# Sheet2.net
KiCad netlist of a schematic drawn in Altium Designer
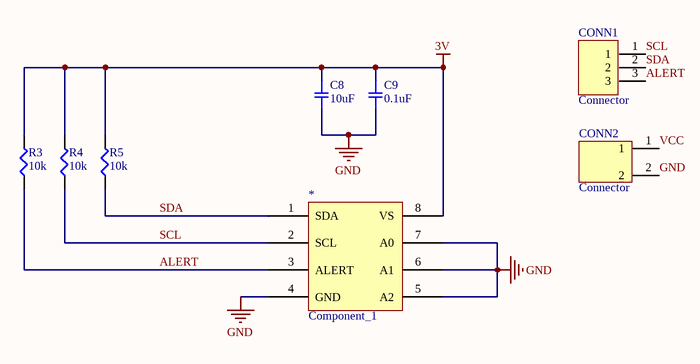
[diagram p0: Sheet2.SchDoc]

(export (version "E")
  (design (tool "Eeschema 10.0.6"))
  (components
    (comp (ref "*")
      (value "Component_1")
      (footprint "TMP75C")
      (libsource (lib "TMP75C") (part "Component_1"))
    )
    (comp (ref "C8")
      (value "10uF")
      (footprint "SMD-0805C")
      (description "Cap Ceramic 10uF 25V X5R 10% 0805")
      (fields
        (field (name "PART NUMBER") "CL21A106KAFN3NE")
        (field (name "MANUFACTURER") "Samsung Electro-Mechanics")
      )
      (libsource (lib "capacitor_0805") (part "CL21A106KAFN3NE"))
    )
    (comp (ref "C9")
      (value "0.1uF")
      (footprint "SMD-0805C")
      (description "CAP CER 0.1uF 50V X7T 0805")
      (fields
        (field (name "PART NUMBER") "GC321AD72E103KX01D")
        (field (name "MANUFACTURER") "Samsung Electro-Mechanics")
      )
      (libsource (lib "capacitor_0805") (part "CL21B104JBCNNNC"))
    )
    (comp (ref "CONN1")
      (value "Connector")
      (footprint "1x3x2.54 Pin Header TH V")
      (libsource (lib "Connectors") (part "Header 1x3"))
    )
    (comp (ref "CONN2")
      (value "Connector")
      (footprint "1x2x2.54 Pin Header TH V")
      (libsource (lib "Connectors") (part "Header 1x2"))
    )
    (comp (ref "R3")
      (value "10k")
      (footprint "SMD-0805-RES")
      (description "RES SMD 10K OHM 5% 1/2W 0805")
      (fields (field (name "PART NUMBER") "ERJ-P6WJ103V") (field (name "DIGI-KEY PART NUMBER") "P16966CT-ND"))
      (libsource (lib "Panasonic_ERJ_0805") (part "ERJ-P6WJ103V"))
    )
    (comp (ref "R4")
      (value "10k")
      (footprint "SMD-0805-RES")
      (description "RES SMD 10K OHM 5% 1/2W 0805")
      (fields (field (name "PART NUMBER") "ERJ-P6WJ103V") (field (name "DIGI-KEY PART NUMBER") "P16966CT-ND"))
      (libsource (lib "Panasonic_ERJ_0805") (part "ERJ-P6WJ103V"))
    )
    (comp (ref "R5")
      (value "10k")
      (footprint "SMD-0805-RES")
      (description "RES SMD 10K OHM 5% 1/2W 0805")
      (fields (field (name "PART NUMBER") "ERJ-P6WJ103V") (field (name "DIGI-KEY PART NUMBER") "P16966CT-ND"))
      (libsource (lib "Panasonic_ERJ_0805") (part "ERJ-P6WJ103V"))
    )
  )
  (nets
    (net (code "1") (name "/ALERT") (class "Default")
      (node (ref "*") (pin "3") (pinfunction "ALERT_3") (pintype "passive"))
      (node (ref "CONN1") (pin "3") (pinfunction "3_3") (pintype "passive"))
      (node (ref "R3") (pin "1") (pinfunction "1_1") (pintype "passive"))
    )
    (net (code "2") (name "/SCL") (class "Default")
      (node (ref "*") (pin "2") (pinfunction "SCL_2") (pintype "passive"))
      (node (ref "CONN1") (pin "1") (pinfunction "1_1") (pintype "passive"))
      (node (ref "R4") (pin "1") (pinfunction "1_1") (pintype "passive"))
    )
    (net (code "3") (name "/SDA") (class "Default")
      (node (ref "*") (pin "1") (pinfunction "SDA_1") (pintype "passive"))
      (node (ref "CONN1") (pin "2") (pinfunction "2_2") (pintype "passive"))
      (node (ref "R5") (pin "1") (pinfunction "1_1") (pintype "passive"))
    )
    (net (code "4") (name "/VCC") (class "Default")
      (node (ref "CONN2") (pin "1") (pinfunction "1_1") (pintype "passive"))
    )
    (net (code "5") (name "3V") (class "Default")
      (node (ref "*") (pin "8") (pinfunction "VS_8") (pintype "passive"))
      (node (ref "C8") (pin "1") (pinfunction "1_1") (pintype "passive"))
      (node (ref "C9") (pin "1") (pinfunction "1_1") (pintype "passive"))
      (node (ref "R3") (pin "2") (pinfunction "2_2") (pintype "passive"))
      (node (ref "R4") (pin "2") (pinfunction "2_2") (pintype "passive"))
      (node (ref "R5") (pin "2") (pinfunction "2_2") (pintype "passive"))
    )
    (net (code "6") (name "GND") (class "Default")
      (node (ref "*") (pin "4") (pinfunction "GND_4") (pintype "passive"))
      (node (ref "*") (pin "5") (pinfunction "A2_5") (pintype "passive"))
      (node (ref "*") (pin "6") (pinfunction "A1_6") (pintype "passive"))
      (node (ref "*") (pin "7") (pinfunction "A0_7") (pintype "passive"))
      (node (ref "C8") (pin "2") (pinfunction "2_2") (pintype "passive"))
      (node (ref "C9") (pin "2") (pinfunction "2_2") (pintype "passive"))
      (node (ref "CONN2") (pin "2") (pinfunction "2_2") (pintype "passive"))
    )
  )
)
